# Schematic.net
KiCad netlist of a schematic drawn in Altium Designer
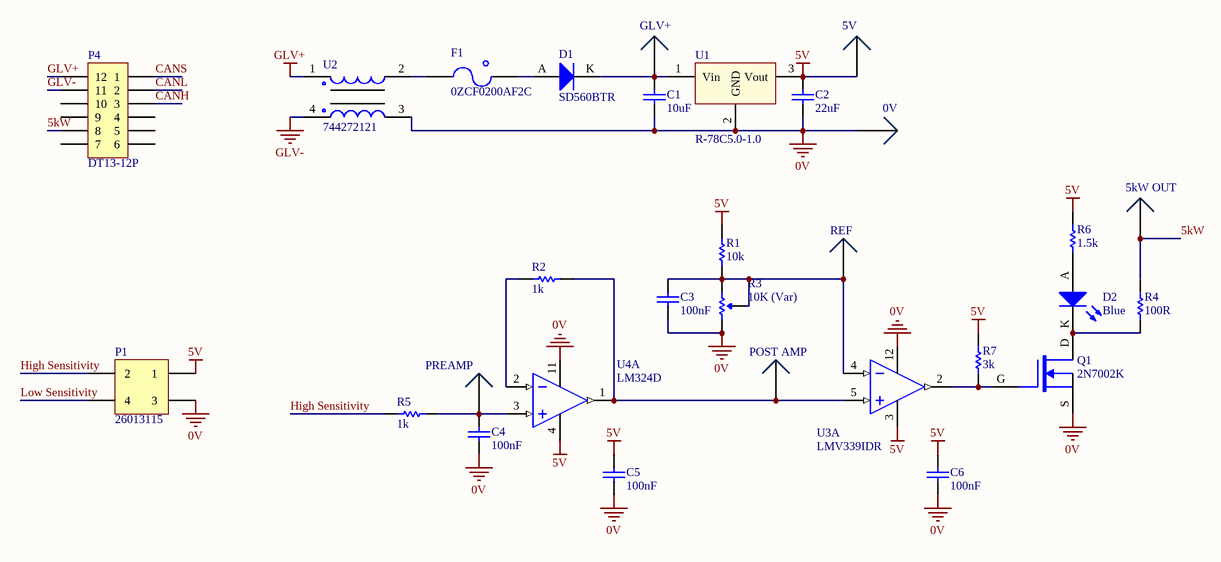
[diagram p0: Schematic.SchDoc]

(export (version "E")
  (design (tool "Eeschema 10.0.6"))
  (components
    (comp (ref "0V")
      (value "0mm")
      (footprint "TH Test Point")
      (fields (field (name "PART NUMBER") "TH Test Point") (field (name "CONTACT") "NA"))
      (libsource (lib "ts_20-standard-connectors") (part "Test Point"))
    )
    (comp (ref "5kW OUT")
      (value "0mm")
      (footprint "TH Test Point")
      (fields (field (name "PART NUMBER") "TH Test Point") (field (name "CONTACT") "NA"))
      (libsource (lib "ts_20-standard-connectors") (part "Test Point"))
    )
    (comp (ref "5V")
      (value "0mm")
      (footprint "TH Test Point")
      (fields (field (name "PART NUMBER") "TH Test Point") (field (name "CONTACT") "NA"))
      (libsource (lib "ts_20-standard-connectors") (part "Test Point"))
    )
    (comp (ref "C1")
      (value "10uF")
      (footprint "0805")
      (fields
        (field (name "PART NUMBER") "GRM21BR6YA106KE43L")
        (field (name "TOLERANCE") "10%")
        (field (name "MANUFACTURER") "muRata")
      )
      (libsource (lib "ts_20-standard-library") (part "Capacitor"))
    )
    (comp (ref "C2")
      (value "22uF")
      (footprint "1206")
      (fields
        (field (name "PART NUMBER") "CC1206MKX5R7BB226")
        (field (name "TOLERANCE") "20%")
        (field (name "MANUFACTURER") "YAGEO")
      )
      (libsource (lib "ts_20-standard-library") (part "Capacitor"))
    )
    (comp (ref "C3")
      (value "100nF")
      (footprint "0805")
      (fields
        (field (name "PART NUMBER") "GCM21BR71E104KA37L")
        (field (name "TOLERANCE") "10%")
        (field (name "MANUFACTURER") "muRata")
      )
      (libsource (lib "ts_20-standard-library") (part "Capacitor"))
    )
    (comp (ref "C4")
      (value "100nF")
      (footprint "0805")
      (fields
        (field (name "PART NUMBER") "GCM21BR71E104KA37L")
        (field (name "TOLERANCE") "10%")
        (field (name "MANUFACTURER") "muRata")
      )
      (libsource (lib "ts_20-standard-library") (part "Capacitor"))
    )
    (comp (ref "C5")
      (value "100nF")
      (footprint "0805")
      (fields
        (field (name "PART NUMBER") "GCM21BR71E104KA37L")
        (field (name "TOLERANCE") "10%")
        (field (name "MANUFACTURER") "muRata")
      )
      (libsource (lib "ts_20-standard-library") (part "Capacitor"))
    )
    (comp (ref "C6")
      (value "100nF")
      (footprint "0805")
      (fields
        (field (name "PART NUMBER") "GCM21BR71E104KA37L")
        (field (name "TOLERANCE") "10%")
        (field (name "MANUFACTURER") "muRata")
      )
      (libsource (lib "ts_20-standard-library") (part "Capacitor"))
    )
    (comp (ref "D1")
      (value "SD560BTR")
      (footprint "SMB Diode")
      (description "1.2V_F 600V 5A SMB")
      (fields
        (field (name "MANUFACTURER") "SMC Diode Solutions")
        (field (name "DIGIKEY PART NUMBER") "1655-1530-2-ND")
      )
      (libsource (lib "ts_20-standard-library") (part "Diode"))
    )
    (comp (ref "D2")
      (value "Blue")
      (footprint "0805 LED")
      (description "LED BLUE CLEAR 2012 SMD")
      (fields
        (field (name "PART NUMBER") "SML-MN2BCTT86C")
        (field (name "MANUFACTURER") "ROHM Semiconductor")
      )
      (libsource (lib "ts_20-standard-library") (part "LED"))
    )
    (comp (ref "F1")
      (value "0ZCF0200AF2C")
      (footprint "2920")
      (description "SMD 24V 2A Fuse")
      (fields
        (field (name "MANUFACTURER") "Bel Fuse Inc")
        (field (name "DIGIKEY PART NUMBER") "507-1749-2-ND")
      )
      (libsource (lib "ts_20-standard-library") (part "PTC Fuse"))
    )
    (comp (ref "GLV+")
      (value "0mm")
      (footprint "TH Test Point")
      (fields (field (name "PART NUMBER") "TH Test Point") (field (name "CONTACT") "NA"))
      (libsource (lib "ts_20-standard-connectors") (part "Test Point"))
    )
    (comp (ref "P1")
      (value "26013115")
      (footprint "26013115")
      (fields (field (name "DIGIKEY PART NUMBER") "WM13112-ND") (field (name "CONTACT") "Brass"))
      (libsource (lib "ts_20-standard-connectors") (part "26013115"))
    )
    (comp (ref "P4")
      (value "DT13-12P")
      (footprint "DT13-12P")
      (fields (field (name "DIGIKEY PART NUMBER") "1734-1451-ND") (field (name "CONTACT") "Nickel"))
      (libsource (lib "ts_20-standard-connectors") (part "DT13-12P"))
    )
    (comp (ref "POST AMP")
      (value "0mm")
      (footprint "TH Test Point")
      (fields (field (name "PART NUMBER") "TH Test Point") (field (name "CONTACT") "NA"))
      (libsource (lib "ts_20-standard-connectors") (part "Test Point"))
    )
    (comp (ref "PREAMP")
      (value "0mm")
      (footprint "TH Test Point")
      (fields (field (name "PART NUMBER") "TH Test Point") (field (name "CONTACT") "NA"))
      (libsource (lib "ts_20-standard-connectors") (part "Test Point"))
    )
    (comp (ref "Q1")
      (value "2N7002K")
      (footprint "ON SOT-23 MOSFET")
      (description "60V 380mA, NFET MOSTFET (Small Signal)")
      (fields
        (field (name "MANUFACTURER") "ON Semiconductor")
        (field (name "DIGIKEY PART NUMBER") "2N7002KCT-ND")
        (field (name "PUBLISHER") "Altium Limited")
      )
      (libsource (lib "ts_20-standard-library") (part "MOSFET-N"))
    )
    (comp (ref "R1")
      (value "10k")
      (footprint "0805")
      (fields
        (field (name "PART NUMBER") "RC0805FR0710KL")
        (field (name "MANUFACTURER") "YAGEO")
        (field (name "TOLERANCE") "0.01")
      )
      (libsource (lib "ts_20-standard-library") (part "Resistor"))
    )
    (comp (ref "R2")
      (value "1k")
      (footprint "0805")
      (fields
        (field (name "PART NUMBER") "RC0805FR071KL")
        (field (name "MANUFACTURER") "YAGEO")
        (field (name "TOLERANCE") "0.01")
      )
      (libsource (lib "ts_20-standard-library") (part "Resistor"))
    )
    (comp (ref "R3")
      (value "10K (Var)")
      (footprint "B 3296")
      (fields
        (field (name "PART NUMBER") "3296W-1-103LF")
        (field (name "MANUFACTURER") "Bournes Inc")
        (field (name "TOLERANCE") "0.1")
      )
      (libsource (lib "ts_20-standard-library") (part "Resistor (Potentiometer)"))
    )
    (comp (ref "R4")
      (value "100R")
      (footprint "0805")
      (fields
        (field (name "PART NUMBER") "RC0805FR07100RL")
        (field (name "MANUFACTURER") "YAGEO")
        (field (name "TOLERANCE") "0.01")
      )
      (libsource (lib "ts_20-standard-library") (part "Resistor"))
    )
    (comp (ref "R5")
      (value "1k")
      (footprint "0805")
      (fields
        (field (name "PART NUMBER") "RC0805FR071KL")
        (field (name "MANUFACTURER") "YAGEO")
        (field (name "TOLERANCE") "0.01")
      )
      (libsource (lib "ts_20-standard-library") (part "Resistor"))
    )
    (comp (ref "R6")
      (value "1.5k")
      (footprint "0805")
      (fields
        (field (name "PART NUMBER") "RC0805FR071K5L")
        (field (name "MANUFACTURER") "YAGEO")
        (field (name "TOLERANCE") "0.01")
      )
      (libsource (lib "ts_20-standard-library") (part "Resistor"))
    )
    (comp (ref "R7")
      (value "3k")
      (footprint "0805")
      (fields
        (field (name "PART NUMBER") "RC0805FR073KL")
        (field (name "MANUFACTURER") "YAGEO")
        (field (name "TOLERANCE") "0.01")
      )
      (libsource (lib "ts_20-standard-library") (part "Resistor"))
    )
    (comp (ref "REF")
      (value "0mm")
      (footprint "TH Test Point")
      (fields (field (name "PART NUMBER") "TH Test Point") (field (name "CONTACT") "NA"))
      (libsource (lib "ts_20-standard-connectors") (part "Test Point"))
    )
    (comp (ref "U1")
      (value "R-78C5.0-1.0")
      (footprint "RECOM 3-SIP")
      (description "CONV DC/DC 1A 5V OUT SIP VERT")
      (fields (field (name "MANUFACTURER") "Recom") (field (name "DIGIKEY PART NUMBER") "945-1395-5-ND"))
      (libsource (lib "ts_20-standard-library") (part "R-78C5.0-1.0"))
    )
    (comp (ref "U2")
      (value "744272121")
      (footprint "Wurth 4-PC Pad")
      (description "Common Mode Choke 120UH 2.5A 2LN 460 OHM SMD")
      (fields
        (field (name "MANUFACTURER") "Wurth Electronics Inc")
        (field (name "DIGIKEY PART NUMBER") "732-1489-2-ND")
      )
      (libsource (lib "ts_20-standard-library") (part "744272121"))
    )
    (comp (ref "U3")
      (value "LMV339IDR")
      (footprint "TI 14-SOIC")
      (description "Comparator General Purpose Open Collector 14-SOIC")
      (fields
        (field (name "MANUFACTURER") "Texas Instruments")
        (field (name "DIGIKEY PART NUMBER") "296-6611-2-ND")
      )
      (libsource (lib "ts_20-standard-library") (part "LMV339IDR"))
    )
    (comp (ref "U4")
      (value "LM324D")
      (footprint "TI 14-SOIC")
      (description "IC OPAMP GP 4 CIRCUIT 14SOIC")
      (fields
        (field (name "MANUFACTURER") "Texas Instruments")
        (field (name "DIGIKEY PART NUMBER") "296-1390-5-ND")
      )
      (libsource (lib "ts_20-standard-library") (part "LM324D"))
    )
  )
  (nets
    (net (code "1") (name "/5kW") (class "Default")
      (node (ref "5kW OUT") (pin "1") (pinfunction "1_1") (pintype "passive"))
      (node (ref "P4") (pin "8") (pinfunction "8_8") (pintype "passive"))
      (node (ref "R4") (pin "2") (pinfunction "2_2") (pintype "passive"))
    )
    (net (code "2") (name "/CANH") (class "Default")
      (node (ref "P4") (pin "3") (pinfunction "3_3") (pintype "power_in"))
    )
    (net (code "3") (name "/CANL") (class "Default")
      (node (ref "P4") (pin "2") (pinfunction "2_2") (pintype "power_in"))
    )
    (net (code "4") (name "/CANS") (class "Default")
      (node (ref "P4") (pin "1") (pinfunction "1_1") (pintype "power_in"))
    )
    (net (code "5") (name "/High Sensitivity") (class "Default")
      (node (ref "P1") (pin "2") (pinfunction "2_2") (pintype "passive"))
      (node (ref "R5") (pin "1") (pinfunction "1_1") (pintype "passive"))
    )
    (net (code "6") (name "/Low Sensitivity") (class "Default")
      (node (ref "P1") (pin "4") (pinfunction "4_4") (pintype "passive"))
    )
    (net (code "7") (name "0V") (class "Default")
      (node (ref "0V") (pin "1") (pinfunction "1_1") (pintype "passive"))
      (node (ref "C1") (pin "1") (pinfunction "1_1") (pintype "passive"))
      (node (ref "C2") (pin "1") (pinfunction "1_1") (pintype "passive"))
      (node (ref "C3") (pin "1") (pinfunction "1_1") (pintype "passive"))
      (node (ref "C4") (pin "1") (pinfunction "1_1") (pintype "passive"))
      (node (ref "C5") (pin "1") (pinfunction "1_1") (pintype "passive"))
      (node (ref "C6") (pin "1") (pinfunction "1_1") (pintype "passive"))
      (node (ref "P1") (pin "3") (pinfunction "3_3") (pintype "passive"))
      (node (ref "Q1") (pin "S") (pinfunction "S_S") (pintype "passive"))
      (node (ref "R3") (pin "3") (pinfunction "CW_3") (pintype "passive"))
      (node (ref "U1") (pin "2") (pinfunction "GND_2") (pintype "passive"))
      (node (ref "U2") (pin "3") (pinfunction "3_3") (pintype "power_in"))
      (node (ref "U3") (pin "12") (pinfunction "V-_12") (pintype "power_in"))
      (node (ref "U4") (pin "11") (pinfunction "GND_11") (pintype "power_in"))
    )
    (net (code "8") (name "5V") (class "Default")
      (node (ref "5V") (pin "1") (pinfunction "1_1") (pintype "passive"))
      (node (ref "C2") (pin "2") (pinfunction "2_2") (pintype "passive"))
      (node (ref "C5") (pin "2") (pinfunction "2_2") (pintype "passive"))
      (node (ref "C6") (pin "2") (pinfunction "2_2") (pintype "passive"))
      (node (ref "P1") (pin "1") (pinfunction "1_1") (pintype "passive"))
      (node (ref "R1") (pin "2") (pinfunction "2_2") (pintype "passive"))
      (node (ref "R6") (pin "2") (pinfunction "2_2") (pintype "passive"))
      (node (ref "R7") (pin "2") (pinfunction "2_2") (pintype "passive"))
      (node (ref "U1") (pin "3") (pinfunction "Vout_3") (pintype "passive"))
      (node (ref "U3") (pin "3") (pinfunction "V+_3") (pintype "power_in"))
      (node (ref "U4") (pin "4") (pinfunction "VCC_4") (pintype "power_in"))
    )
    (net (code "9") (name "GLV+") (class "Default")
      (node (ref "P4") (pin "12") (pinfunction "12_12") (pintype "passive"))
      (node (ref "U2") (pin "1") (pinfunction "1_1") (pintype "passive"))
    )
    (net (code "10") (name "GLV-") (class "Default")
      (node (ref "P4") (pin "11") (pinfunction "11_11") (pintype "passive"))
      (node (ref "U2") (pin "4") (pinfunction "4_4") (pintype "passive"))
    )
    (net (code "11") (name "Net-(C4-Pad2)") (class "Default")
      (node (ref "C4") (pin "2") (pinfunction "2_2") (pintype "passive"))
      (node (ref "PREAMP") (pin "1") (pinfunction "1_1") (pintype "passive"))
      (node (ref "R5") (pin "2") (pinfunction "2_2") (pintype "passive"))
      (node (ref "U4") (pin "3") (pinfunction "1IN+_3") (pintype "input"))
    )
    (net (code "12") (name "Net-(D1-PadA)") (class "Default")
      (node (ref "D1") (pin "A") (pinfunction "A_A") (pintype "passive"))
      (node (ref "F1") (pin "2") (pinfunction "2_2") (pintype "passive"))
    )
    (net (code "13") (name "Net-(D2-PadA)") (class "Default")
      (node (ref "D2") (pin "A") (pinfunction "A_A") (pintype "passive"))
      (node (ref "R6") (pin "1") (pinfunction "1_1") (pintype "passive"))
    )
    (net (code "14") (name "Net-(D2-PadK)") (class "Default")
      (node (ref "D2") (pin "K") (pinfunction "K_K") (pintype "passive"))
      (node (ref "Q1") (pin "D") (pinfunction "D_D") (pintype "passive"))
      (node (ref "R4") (pin "1") (pinfunction "1_1") (pintype "passive"))
    )
    (net (code "15") (name "Net-(F1-Pad1)") (class "Default")
      (node (ref "F1") (pin "1") (pinfunction "1_1") (pintype "passive"))
      (node (ref "U2") (pin "2") (pinfunction "2_2") (pintype "passive"))
    )
    (net (code "16") (name "Net-(R2-Pad1)") (class "Default")
      (node (ref "R2") (pin "1") (pinfunction "1_1") (pintype "passive"))
      (node (ref "U4") (pin "2") (pinfunction "1IN+_2") (pintype "input"))
    )
    (net (code "17") (name "Net-(R3-CCW)") (class "Default")
      (node (ref "C3") (pin "2") (pinfunction "2_2") (pintype "passive"))
      (node (ref "R1") (pin "1") (pinfunction "1_1") (pintype "passive"))
      (node (ref "R3") (pin "1") (pinfunction "CCW_1") (pintype "passive"))
      (node (ref "R3") (pin "2") (pinfunction "Wiper_2") (pintype "passive"))
      (node (ref "REF") (pin "1") (pinfunction "1_1") (pintype "passive"))
      (node (ref "U3") (pin "4") (pinfunction "IN_A-_4") (pintype "input"))
    )
    (net (code "18") (name "Net-(U1-Vin)") (class "Default")
      (node (ref "C1") (pin "2") (pinfunction "2_2") (pintype "passive"))
      (node (ref "D1") (pin "K") (pinfunction "K_K") (pintype "passive"))
      (node (ref "GLV+") (pin "1") (pinfunction "1_1") (pintype "passive"))
      (node (ref "U1") (pin "1") (pinfunction "Vin_1") (pintype "passive"))
    )
    (net (code "19") (name "Net-(U3A-IN_A+)") (class "Default")
      (node (ref "POST AMP") (pin "1") (pinfunction "1_1") (pintype "passive"))
      (node (ref "R2") (pin "2") (pinfunction "2_2") (pintype "passive"))
      (node (ref "U3") (pin "5") (pinfunction "IN_A+_5") (pintype "input"))
      (node (ref "U4") (pin "1") (pinfunction "1OUT_1") (pintype "output"))
    )
    (net (code "20") (name "Net-(U3A-OUT_A)") (class "Default")
      (node (ref "Q1") (pin "G") (pinfunction "G_G") (pintype "passive"))
      (node (ref "R7") (pin "1") (pinfunction "1_1") (pintype "passive"))
      (node (ref "U3") (pin "2") (pinfunction "OUT_A_2") (pintype "output"))
    )
    (net (code "21") (name "unconnected-(P4-Pad4)") (class "Default")
      (node (ref "P4") (pin "4") (pinfunction "4_4") (pintype "power_in"))
    )
    (net (code "22") (name "unconnected-(P4-Pad5)") (class "Default")
      (node (ref "P4") (pin "5") (pinfunction "5_5") (pintype "power_in"))
    )
    (net (code "23") (name "unconnected-(P4-Pad6)") (class "Default")
      (node (ref "P4") (pin "6") (pinfunction "6_6") (pintype "power_in"))
    )
    (net (code "24") (name "unconnected-(P4-Pad7)") (class "Default")
      (node (ref "P4") (pin "7") (pinfunction "7_7") (pintype "passive"))
    )
    (net (code "25") (name "unconnected-(P4-Pad9)") (class "Default")
      (node (ref "P4") (pin "9") (pinfunction "9_9") (pintype "passive"))
    )
    (net (code "26") (name "unconnected-(P4-Pad10)") (class "Default")
      (node (ref "P4") (pin "10") (pinfunction "10_10") (pintype "passive"))
    )
  )
)
